# MagController.net
KiCad netlist of a schematic drawn in EAGLE
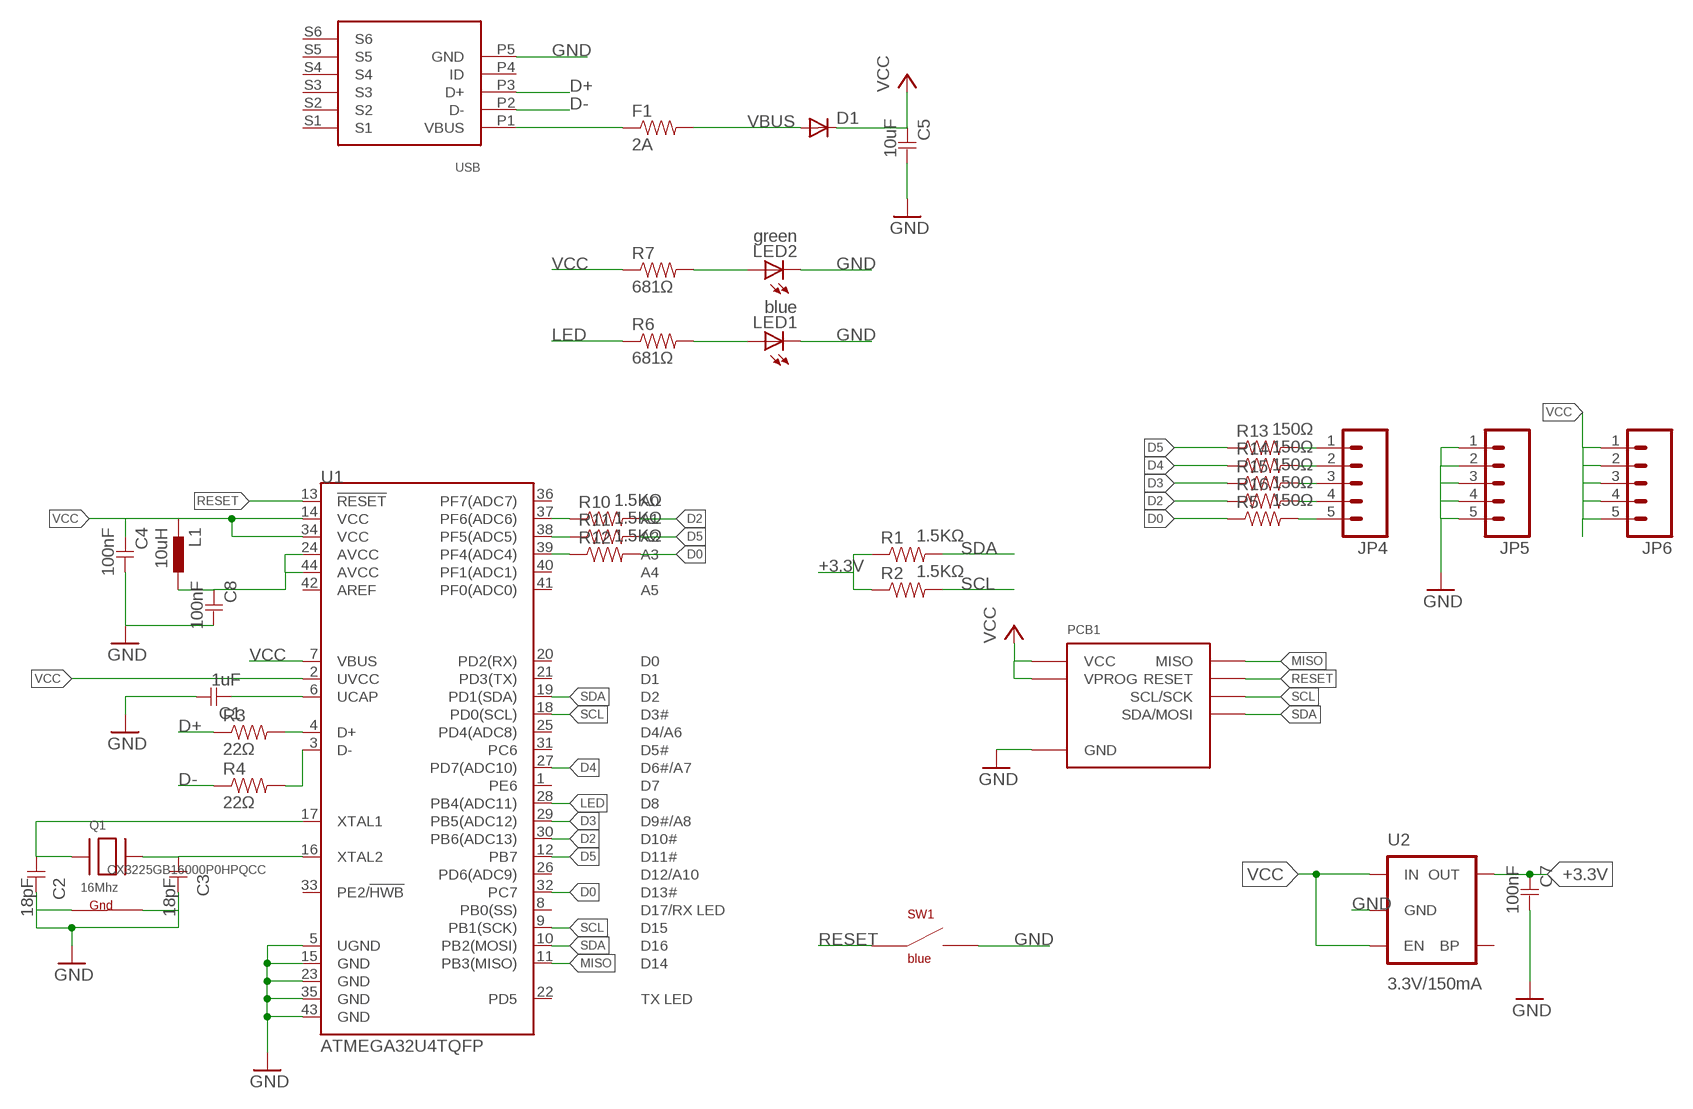
[diagram p0: schematic, sheet 1]

(export (version "E")
  (design (tool "Eeschema 10.0.6"))
  (components
    (comp (ref "C1")
      (value "1uF")
      (footprint "eagle-import:0603")
      (fields (field (name "PARTNUM") "C0603C105K4RACTU"))
      (libsource (lib "eagle-import") (part "CAPACITOR-1UF"))
    )
    (comp (ref "C2")
      (value "18pF")
      (footprint "eagle-import:0603")
      (fields (field (name "PARTNUM") "C0603C180J5GACTU"))
      (libsource (lib "eagle-import") (part "CAPACITOR-18PF"))
    )
    (comp (ref "C3")
      (value "18pF")
      (footprint "eagle-import:0603")
      (fields (field (name "PARTNUM") "C0603C180J5GACTU"))
      (libsource (lib "eagle-import") (part "CAPACITOR-18PF"))
    )
    (comp (ref "C4")
      (value "100nF")
      (footprint "eagle-import:0603")
      (fields (field (name "PARTNUM") "C0603C104K5RACTU"))
      (libsource (lib "eagle-import") (part "CAPACITOR-100NF"))
    )
    (comp (ref "C5")
      (value "10uF")
      (footprint "eagle-import:0603")
      (fields (field (name "PARTNUM") "GRM188R60J106ME47D"))
      (libsource (lib "eagle-import") (part "CAPACITOR-10UF"))
    )
    (comp (ref "C7")
      (value "100nF")
      (footprint "eagle-import:0603")
      (fields (field (name "PARTNUM") "C0603C104K5RACTU"))
      (libsource (lib "eagle-import") (part "CAPACITOR-100NF"))
    )
    (comp (ref "C8")
      (value "100nF")
      (footprint "eagle-import:0603")
      (fields (field (name "PARTNUM") "C0603C104K5RACTU"))
      (libsource (lib "eagle-import") (part "CAPACITOR-100NF"))
    )
    (comp (ref "D1")
      (value "DIODESMA")
      (footprint "eagle-import:SMA-DIODE")
      (fields (field (name "PARTNUM") "SSA33L-E3/61TGICT-ND"))
      (libsource (lib "eagle-import") (part "DIODESMA"))
    )
    (comp (ref "F1")
      (value "2A")
      (footprint "eagle-import:0603")
      (fields (field (name "PARTNUM") "MF-PSMF110X-2"))
      (libsource (lib "eagle-import") (part "RESISTOR-0603"))
    )
    (comp (ref "JP4")
      (value "M05NO_SILK")
      (footprint "eagle-import:1X05_NO_SILK")
      (libsource (lib "eagle-import") (part "M05NO_SILK"))
    )
    (comp (ref "JP5")
      (value "M05NO_SILK")
      (footprint "eagle-import:1X05_NO_SILK")
      (libsource (lib "eagle-import") (part "M05NO_SILK"))
    )
    (comp (ref "JP6")
      (value "M05NO_SILK")
      (footprint "eagle-import:1X05_NO_SILK")
      (libsource (lib "eagle-import") (part "M05NO_SILK"))
    )
    (comp (ref "L1")
      (value "10uH")
      (footprint "eagle-import:0603")
      (fields (field (name "PARTNUM") "LQM18FN100M00"))
      (libsource (lib "eagle-import") (part "INDUCTOR-10UH"))
    )
    (comp (ref "LED1")
      (value "blue")
      (footprint "eagle-import:0805-LED")
      (fields (field (name "PARTNUM") "LTST-C171TBKT"))
      (libsource (lib "eagle-import") (part "LED-0805-BLUE"))
    )
    (comp (ref "LED2")
      (value "green")
      (footprint "eagle-import:0805-LED")
      (fields (field (name "PARTNUM") "LTST-C171GKT"))
      (libsource (lib "eagle-import") (part "LED-0805-GREEN"))
    )
    (comp (ref "PCB1")
      (value "MAGDEVICE")
      (footprint "eagle-import:MAGDEVICE")
      (libsource (lib "eagle-import") (part "MAGDEVICE"))
    )
    (comp (ref "Q1")
      (value "16Mhz")
      (footprint "eagle-import:NX3225")
      (fields (field (name "PARTNUM") "CX3225GB16000P0HPQCC"))
      (libsource (lib "eagle-import") (part "CRYSTAL-NX3225"))
    )
    (comp (ref "R1")
      (value "1.5KΩ")
      (footprint "eagle-import:0603")
      (fields (field (name "PARTNUM") "ERJ-3EKF1501V"))
      (libsource (lib "eagle-import") (part "RESISTOR-1.5KΩ"))
    )
    (comp (ref "R2")
      (value "1.5KΩ")
      (footprint "eagle-import:0603")
      (fields (field (name "PARTNUM") "ERJ-3EKF1501V"))
      (libsource (lib "eagle-import") (part "RESISTOR-1.5KΩ"))
    )
    (comp (ref "R3")
      (value "22Ω")
      (footprint "eagle-import:0603")
      (fields (field (name "PARTNUM") "ERJ-3EKF22R0V"))
      (libsource (lib "eagle-import") (part "RESISTOR-22Ω"))
    )
    (comp (ref "R4")
      (value "22Ω")
      (footprint "eagle-import:0603")
      (fields (field (name "PARTNUM") "ERJ-3EKF22R0V"))
      (libsource (lib "eagle-import") (part "RESISTOR-22Ω"))
    )
    (comp (ref "R5")
      (value "150Ω")
      (footprint "eagle-import:0603")
      (fields (field (name "PARTNUM") "ERJ-3EKF1500V"))
      (libsource (lib "eagle-import") (part "RESISTOR-150Ω"))
    )
    (comp (ref "R6")
      (value "681Ω")
      (footprint "eagle-import:0603")
      (fields (field (name "PARTNUM") "ERJ-3EKF6810V"))
      (libsource (lib "eagle-import") (part "RESISTOR-681Ω"))
    )
    (comp (ref "R7")
      (value "681Ω")
      (footprint "eagle-import:0603")
      (fields (field (name "PARTNUM") "ERJ-3EKF6810V"))
      (libsource (lib "eagle-import") (part "RESISTOR-681Ω"))
    )
    (comp (ref "R10")
      (value "1.5KΩ")
      (footprint "eagle-import:0603")
      (fields (field (name "PARTNUM") "ERJ-3EKF1501V"))
      (libsource (lib "eagle-import") (part "RESISTOR-1.5KΩ"))
    )
    (comp (ref "R11")
      (value "1.5KΩ")
      (footprint "eagle-import:0603")
      (fields (field (name "PARTNUM") "ERJ-3EKF1501V"))
      (libsource (lib "eagle-import") (part "RESISTOR-1.5KΩ"))
    )
    (comp (ref "R12")
      (value "1.5KΩ")
      (footprint "eagle-import:0603")
      (fields (field (name "PARTNUM") "ERJ-3EKF1501V"))
      (libsource (lib "eagle-import") (part "RESISTOR-1.5KΩ"))
    )
    (comp (ref "R13")
      (value "150Ω")
      (footprint "eagle-import:0603")
      (fields (field (name "PARTNUM") "ERJ-3EKF1500V"))
      (libsource (lib "eagle-import") (part "RESISTOR-150Ω"))
    )
    (comp (ref "R14")
      (value "150Ω")
      (footprint "eagle-import:0603")
      (fields (field (name "PARTNUM") "ERJ-3EKF1500V"))
      (libsource (lib "eagle-import") (part "RESISTOR-150Ω"))
    )
    (comp (ref "R15")
      (value "150Ω")
      (footprint "eagle-import:0603")
      (fields (field (name "PARTNUM") "ERJ-3EKF1500V"))
      (libsource (lib "eagle-import") (part "RESISTOR-150Ω"))
    )
    (comp (ref "R16")
      (value "150Ω")
      (footprint "eagle-import:0603")
      (fields (field (name "PARTNUM") "ERJ-3EKF1500V"))
      (libsource (lib "eagle-import") (part "RESISTOR-150Ω"))
    )
    (comp (ref "SW1")
      (value "blue")
      (footprint "eagle-import:BOURNS-7914J")
      (fields (field (name "PARTNUM") "7914J-1-000E"))
      (libsource (lib "eagle-import") (part "SWITCHBOURNS-7914J"))
    )
    (comp (ref "U1")
      (value "ATMEGA32U4TQFP")
      (footprint "eagle-import:SPARKFUN-DIGITALIC_TQFP44")
      (fields (field (name "PARTNUM") "ATMEGA32U4-AU"))
      (libsource (lib "eagle-import") (part "ATMEGA32U4TQFP"))
    )
    (comp (ref "U2")
      (value "3.3V/150mA")
      (footprint "eagle-import:SOT23-5")
      (fields (field (name "PARTNUM") "MIC5205-3.3YM5 TR"))
      (libsource (lib "eagle-import") (part "V_REG_MIC52053.3V"))
    )
    (comp (ref "U3")
      (value "USBFCI-MICROB")
      (footprint "eagle-import:USB-MICROB-FCI")
      (fields (field (name "PARTNUM") "10118194-0001LF"))
      (libsource (lib "eagle-import") (part "USBFCI-MICROB"))
    )
  )
  (nets
    (net (code "1") (name "+3.3V") (class "Default")
      (node (ref "C7") (pin "1") (pinfunction "1_1") (pintype "passive"))
      (node (ref "R1") (pin "1") (pinfunction "1_1") (pintype "passive"))
      (node (ref "R2") (pin "1") (pinfunction "1_1") (pintype "passive"))
      (node (ref "U2") (pin "5") (pinfunction "OUT_5") (pintype "passive"))
    )
    (net (code "2") (name "/D+") (class "Default")
      (node (ref "R3") (pin "1") (pinfunction "1_1") (pintype "passive"))
      (node (ref "U3") (pin "P3") (pinfunction "D+_P3") (pintype "bidirectional"))
    )
    (net (code "3") (name "/D-") (class "Default")
      (node (ref "R4") (pin "1") (pinfunction "1_1") (pintype "passive"))
      (node (ref "U3") (pin "P2") (pinfunction "D-_P2") (pintype "bidirectional"))
    )
    (net (code "4") (name "/VBUS") (class "Default")
      (node (ref "D1") (pin "A") (pinfunction "A_A") (pintype "passive"))
      (node (ref "F1") (pin "2") (pinfunction "2_2") (pintype "passive"))
    )
    (net (code "5") (name "D0") (class "Default")
      (node (ref "R12") (pin "2") (pinfunction "2_2") (pintype "passive"))
      (node (ref "R5") (pin "1") (pinfunction "1_1") (pintype "passive"))
      (node (ref "U1") (pin "32") (pinfunction "PC7_32") (pintype "bidirectional"))
    )
    (net (code "6") (name "D2") (class "Default")
      (node (ref "R10") (pin "2") (pinfunction "2_2") (pintype "passive"))
      (node (ref "R16") (pin "1") (pinfunction "1_1") (pintype "passive"))
      (node (ref "U1") (pin "30") (pinfunction "PB6(ADC13)_30") (pintype "bidirectional"))
    )
    (net (code "7") (name "D3") (class "Default")
      (node (ref "R15") (pin "1") (pinfunction "1_1") (pintype "passive"))
      (node (ref "U1") (pin "29") (pinfunction "PB5(ADC12)_29") (pintype "bidirectional"))
    )
    (net (code "8") (name "D4") (class "Default")
      (node (ref "R14") (pin "1") (pinfunction "1_1") (pintype "passive"))
      (node (ref "U1") (pin "27") (pinfunction "PD7(ADC10)_27") (pintype "bidirectional"))
    )
    (net (code "9") (name "D5") (class "Default")
      (node (ref "R11") (pin "2") (pinfunction "2_2") (pintype "passive"))
      (node (ref "R13") (pin "1") (pinfunction "1_1") (pintype "passive"))
      (node (ref "U1") (pin "12") (pinfunction "PB7_12") (pintype "bidirectional"))
    )
    (net (code "10") (name "GND") (class "Default")
      (node (ref "C1") (pin "2") (pinfunction "2_2") (pintype "passive"))
      (node (ref "C2") (pin "2") (pinfunction "2_2") (pintype "passive"))
      (node (ref "C3") (pin "2") (pinfunction "2_2") (pintype "passive"))
      (node (ref "C4") (pin "2") (pinfunction "2_2") (pintype "passive"))
      (node (ref "C5") (pin "2") (pinfunction "2_2") (pintype "passive"))
      (node (ref "C7") (pin "2") (pinfunction "2_2") (pintype "passive"))
      (node (ref "C8") (pin "2") (pinfunction "2_2") (pintype "passive"))
      (node (ref "JP5") (pin "1") (pinfunction "1_1") (pintype "passive"))
      (node (ref "JP5") (pin "2") (pinfunction "2_2") (pintype "passive"))
      (node (ref "JP5") (pin "3") (pinfunction "3_3") (pintype "passive"))
      (node (ref "JP5") (pin "4") (pinfunction "4_4") (pintype "passive"))
      (node (ref "JP5") (pin "5") (pinfunction "5_5") (pintype "passive"))
      (node (ref "LED1") (pin "C") (pinfunction "C_C") (pintype "passive"))
      (node (ref "LED2") (pin "C") (pinfunction "C_C") (pintype "passive"))
      (node (ref "PCB1") (pin "GNDA") (pinfunction "GND_GNDA") (pintype "bidirectional"))
      (node (ref "PCB1") (pin "GNDB") (pinfunction "GND_GNDB") (pintype "bidirectional"))
      (node (ref "Q1") (pin "2") (pinfunction "G1_2") (pintype "power_in"))
      (node (ref "Q1") (pin "4") (pinfunction "G2_4") (pintype "power_in"))
      (node (ref "SW1") (pin "NEG$1") (pinfunction "NEG1_NEG$1") (pintype "bidirectional"))
      (node (ref "SW1") (pin "NEG$2") (pinfunction "NEG1_NEG$2") (pintype "bidirectional"))
      (node (ref "U1") (pin "15") (pinfunction "GND_15") (pintype "bidirectional"))
      (node (ref "U1") (pin "23") (pinfunction "GND_23") (pintype "bidirectional"))
      (node (ref "U1") (pin "35") (pinfunction "GND_35") (pintype "bidirectional"))
      (node (ref "U1") (pin "43") (pinfunction "GND_43") (pintype "bidirectional"))
      (node (ref "U1") (pin "5") (pinfunction "UGND_5") (pintype "bidirectional"))
      (node (ref "U2") (pin "2") (pinfunction "GND_2") (pintype "input"))
      (node (ref "U3") (pin "P5") (pinfunction "GND_P5") (pintype "bidirectional"))
    )
    (net (code "11") (name "LED") (class "Default")
      (node (ref "R6") (pin "1") (pinfunction "1_1") (pintype "passive"))
      (node (ref "U1") (pin "28") (pinfunction "PB4(ADC11)_28") (pintype "bidirectional"))
    )
    (net (code "12") (name "MISO") (class "Default")
      (node (ref "PCB1") (pin "MISO") (pinfunction "MISO_MISO") (pintype "bidirectional"))
      (node (ref "U1") (pin "11") (pinfunction "PB3(MISO)_11") (pintype "bidirectional"))
    )
    (net (code "13") (name "Net-(C8-Pad1)") (class "Default")
      (node (ref "C8") (pin "1") (pinfunction "1_1") (pintype "passive"))
      (node (ref "L1") (pin "2") (pinfunction "2_2") (pintype "passive"))
      (node (ref "U1") (pin "24") (pinfunction "AVCC_24") (pintype "bidirectional"))
      (node (ref "U1") (pin "44") (pinfunction "AVCC_44") (pintype "bidirectional"))
    )
    (net (code "14") (name "Net-(JP4-Pad1)") (class "Default")
      (node (ref "JP4") (pin "1") (pinfunction "1_1") (pintype "passive"))
      (node (ref "R13") (pin "2") (pinfunction "2_2") (pintype "passive"))
    )
    (net (code "15") (name "Net-(JP4-Pad2)") (class "Default")
      (node (ref "JP4") (pin "2") (pinfunction "2_2") (pintype "passive"))
      (node (ref "R14") (pin "2") (pinfunction "2_2") (pintype "passive"))
    )
    (net (code "16") (name "Net-(JP4-Pad3)") (class "Default")
      (node (ref "JP4") (pin "3") (pinfunction "3_3") (pintype "passive"))
      (node (ref "R15") (pin "2") (pinfunction "2_2") (pintype "passive"))
    )
    (net (code "17") (name "Net-(JP4-Pad4)") (class "Default")
      (node (ref "JP4") (pin "4") (pinfunction "4_4") (pintype "passive"))
      (node (ref "R16") (pin "2") (pinfunction "2_2") (pintype "passive"))
    )
    (net (code "18") (name "Net-(JP4-Pad5)") (class "Default")
      (node (ref "JP4") (pin "5") (pinfunction "5_5") (pintype "passive"))
      (node (ref "R5") (pin "2") (pinfunction "2_2") (pintype "passive"))
    )
    (net (code "19") (name "Net-(LED1-PadA)") (class "Default")
      (node (ref "LED1") (pin "A") (pinfunction "A_A") (pintype "passive"))
      (node (ref "R6") (pin "2") (pinfunction "2_2") (pintype "passive"))
    )
    (net (code "20") (name "Net-(LED2-PadA)") (class "Default")
      (node (ref "LED2") (pin "A") (pinfunction "A_A") (pintype "passive"))
      (node (ref "R7") (pin "2") (pinfunction "2_2") (pintype "passive"))
    )
    (net (code "21") (name "Net-(Q1-X1)") (class "Default")
      (node (ref "C2") (pin "1") (pinfunction "1_1") (pintype "passive"))
      (node (ref "Q1") (pin "1") (pinfunction "X1_1") (pintype "bidirectional"))
      (node (ref "U1") (pin "17") (pinfunction "XTAL1_17") (pintype "bidirectional"))
    )
    (net (code "22") (name "Net-(Q1-X2)") (class "Default")
      (node (ref "C3") (pin "1") (pinfunction "1_1") (pintype "passive"))
      (node (ref "Q1") (pin "3") (pinfunction "X2_3") (pintype "bidirectional"))
      (node (ref "U1") (pin "16") (pinfunction "XTAL2_16") (pintype "bidirectional"))
    )
    (net (code "23") (name "Net-(U1-D+)") (class "Default")
      (node (ref "R3") (pin "2") (pinfunction "2_2") (pintype "passive"))
      (node (ref "U1") (pin "4") (pinfunction "D+_4") (pintype "bidirectional"))
    )
    (net (code "24") (name "Net-(U1-D-)") (class "Default")
      (node (ref "R4") (pin "2") (pinfunction "2_2") (pintype "passive"))
      (node (ref "U1") (pin "3") (pinfunction "D-_3") (pintype "bidirectional"))
    )
    (net (code "25") (name "Net-(U1-PF4(ADC4))") (class "Default")
      (node (ref "R12") (pin "1") (pinfunction "1_1") (pintype "passive"))
      (node (ref "U1") (pin "39") (pinfunction "PF4(ADC4)_39") (pintype "bidirectional"))
    )
    (net (code "26") (name "Net-(U1-PF5(ADC5))") (class "Default")
      (node (ref "R11") (pin "1") (pinfunction "1_1") (pintype "passive"))
      (node (ref "U1") (pin "38") (pinfunction "PF5(ADC5)_38") (pintype "bidirectional"))
    )
    (net (code "27") (name "Net-(U1-PF6(ADC6))") (class "Default")
      (node (ref "R10") (pin "1") (pinfunction "1_1") (pintype "passive"))
      (node (ref "U1") (pin "37") (pinfunction "PF6(ADC6)_37") (pintype "bidirectional"))
    )
    (net (code "28") (name "Net-(U1-UCAP)") (class "Default")
      (node (ref "C1") (pin "1") (pinfunction "1_1") (pintype "passive"))
      (node (ref "U1") (pin "6") (pinfunction "UCAP_6") (pintype "bidirectional"))
    )
    (net (code "29") (name "Net-(U3-VBUS)") (class "Default")
      (node (ref "F1") (pin "1") (pinfunction "1_1") (pintype "passive"))
      (node (ref "U3") (pin "P1") (pinfunction "VBUS_P1") (pintype "bidirectional"))
    )
    (net (code "30") (name "RESET") (class "Default")
      (node (ref "PCB1") (pin "RESET") (pinfunction "RESET_RESET") (pintype "bidirectional"))
      (node (ref "SW1") (pin "POS$1") (pinfunction "POS1_POS$1") (pintype "bidirectional"))
      (node (ref "SW1") (pin "POS$2") (pinfunction "POS1_POS$2") (pintype "bidirectional"))
      (node (ref "U1") (pin "13") (pinfunction "~{RESET}_13") (pintype "bidirectional"))
    )
    (net (code "31") (name "SCL") (class "Default")
      (node (ref "PCB1") (pin "SCLA") (pinfunction "SCL/SCK_SCLA") (pintype "bidirectional"))
      (node (ref "PCB1") (pin "SCLB") (pinfunction "SCL/SCK_SCLB") (pintype "bidirectional"))
      (node (ref "R2") (pin "2") (pinfunction "2_2") (pintype "passive"))
      (node (ref "U1") (pin "18") (pinfunction "PD0(SCL)_18") (pintype "bidirectional"))
      (node (ref "U1") (pin "9") (pinfunction "PB1(SCK)_9") (pintype "bidirectional"))
    )
    (net (code "32") (name "SDA") (class "Default")
      (node (ref "PCB1") (pin "SDAA") (pinfunction "SDA/MOSI_SDAA") (pintype "bidirectional"))
      (node (ref "PCB1") (pin "SDAB") (pinfunction "SDA/MOSI_SDAB") (pintype "bidirectional"))
      (node (ref "R1") (pin "2") (pinfunction "2_2") (pintype "passive"))
      (node (ref "U1") (pin "10") (pinfunction "PB2(MOSI)_10") (pintype "bidirectional"))
      (node (ref "U1") (pin "19") (pinfunction "PD1(SDA)_19") (pintype "bidirectional"))
    )
    (net (code "33") (name "VCC") (class "Default")
      (node (ref "C4") (pin "1") (pinfunction "1_1") (pintype "passive"))
      (node (ref "C5") (pin "1") (pinfunction "1_1") (pintype "passive"))
      (node (ref "D1") (pin "C") (pinfunction "C_C") (pintype "passive"))
      (node (ref "JP6") (pin "1") (pinfunction "1_1") (pintype "passive"))
      (node (ref "JP6") (pin "2") (pinfunction "2_2") (pintype "passive"))
      (node (ref "JP6") (pin "3") (pinfunction "3_3") (pintype "passive"))
      (node (ref "JP6") (pin "4") (pinfunction "4_4") (pintype "passive"))
      (node (ref "JP6") (pin "5") (pinfunction "5_5") (pintype "passive"))
      (node (ref "L1") (pin "1") (pinfunction "1_1") (pintype "passive"))
      (node (ref "PCB1") (pin "VCCA") (pinfunction "VCC_VCCA") (pintype "bidirectional"))
      (node (ref "PCB1") (pin "VCCB") (pinfunction "VCC_VCCB") (pintype "bidirectional"))
      (node (ref "PCB1") (pin "VPROG") (pinfunction "VPROG_VPROG") (pintype "bidirectional"))
      (node (ref "R7") (pin "1") (pinfunction "1_1") (pintype "passive"))
      (node (ref "U1") (pin "14") (pinfunction "VCC_14") (pintype "bidirectional"))
      (node (ref "U1") (pin "2") (pinfunction "UVCC_2") (pintype "bidirectional"))
      (node (ref "U1") (pin "34") (pinfunction "VCC_34") (pintype "bidirectional"))
      (node (ref "U1") (pin "7") (pinfunction "VBUS_7") (pintype "bidirectional"))
      (node (ref "U2") (pin "1") (pinfunction "IN_1") (pintype "input"))
      (node (ref "U2") (pin "3") (pinfunction "EN_3") (pintype "input"))
    )
    (net (code "34") (name "unconnected-(U1-AREF-Pad42)") (class "Default")
      (node (ref "U1") (pin "42") (pinfunction "AREF_42") (pintype "bidirectional"))
    )
    (net (code "35") (name "unconnected-(U1-PB0(SS)-Pad8)") (class "Default")
      (node (ref "U1") (pin "8") (pinfunction "PB0(SS)_8") (pintype "bidirectional"))
    )
    (net (code "36") (name "unconnected-(U1-PC6-Pad31)") (class "Default")
      (node (ref "U1") (pin "31") (pinfunction "PC6_31") (pintype "bidirectional"))
    )
    (net (code "37") (name "unconnected-(U1-PD2(RX)-Pad20)") (class "Default")
      (node (ref "U1") (pin "20") (pinfunction "PD2(RX)_20") (pintype "bidirectional"))
    )
    (net (code "38") (name "unconnected-(U1-PD3(TX)-Pad21)") (class "Default")
      (node (ref "U1") (pin "21") (pinfunction "PD3(TX)_21") (pintype "bidirectional"))
    )
    (net (code "39") (name "unconnected-(U1-PD4(ADC8)-Pad25)") (class "Default")
      (node (ref "U1") (pin "25") (pinfunction "PD4(ADC8)_25") (pintype "bidirectional"))
    )
    (net (code "40") (name "unconnected-(U1-PD5-Pad22)") (class "Default")
      (node (ref "U1") (pin "22") (pinfunction "PD5_22") (pintype "bidirectional"))
    )
    (net (code "41") (name "unconnected-(U1-PD6(ADC9)-Pad26)") (class "Default")
      (node (ref "U1") (pin "26") (pinfunction "PD6(ADC9)_26") (pintype "bidirectional"))
    )
    (net (code "42") (name "unconnected-(U1-PE2{slash}~{HWB}-Pad33)") (class "Default")
      (node (ref "U1") (pin "33") (pinfunction "PE2/~{HWB}_33") (pintype "bidirectional"))
    )
    (net (code "43") (name "unconnected-(U1-PE6-Pad1)") (class "Default")
      (node (ref "U1") (pin "1") (pinfunction "PE6_1") (pintype "bidirectional"))
    )
    (net (code "44") (name "unconnected-(U1-PF0(ADC0)-Pad41)") (class "Default")
      (node (ref "U1") (pin "41") (pinfunction "PF0(ADC0)_41") (pintype "bidirectional"))
    )
    (net (code "45") (name "unconnected-(U1-PF1(ADC1)-Pad40)") (class "Default")
      (node (ref "U1") (pin "40") (pinfunction "PF1(ADC1)_40") (pintype "bidirectional"))
    )
    (net (code "46") (name "unconnected-(U1-PF7(ADC7)-Pad36)") (class "Default")
      (node (ref "U1") (pin "36") (pinfunction "PF7(ADC7)_36") (pintype "bidirectional"))
    )
    (net (code "47") (name "unconnected-(U2-BP-Pad4)") (class "Default")
      (node (ref "U2") (pin "4") (pinfunction "BP_4") (pintype "input"))
    )
    (net (code "48") (name "unconnected-(U3-ID-PadP4)") (class "Default")
      (node (ref "U3") (pin "P4") (pinfunction "ID_P4") (pintype "bidirectional"))
    )
    (net (code "49") (name "unconnected-(U3-PadS1)") (class "Default")
      (node (ref "U3") (pin "S1") (pinfunction "S1_S1") (pintype "bidirectional"))
    )
    (net (code "50") (name "unconnected-(U3-PadS2)") (class "Default")
      (node (ref "U3") (pin "S2") (pinfunction "S2_S2") (pintype "bidirectional"))
    )
    (net (code "51") (name "unconnected-(U3-PadS3)") (class "Default")
      (node (ref "U3") (pin "S3") (pinfunction "S3_S3") (pintype "bidirectional"))
    )
    (net (code "52") (name "unconnected-(U3-PadS4)") (class "Default")
      (node (ref "U3") (pin "S4") (pinfunction "S4_S4") (pintype "bidirectional"))
    )
    (net (code "53") (name "unconnected-(U3-PadS5)") (class "Default")
      (node (ref "U3") (pin "S5") (pinfunction "S5_S5") (pintype "bidirectional"))
    )
    (net (code "54") (name "unconnected-(U3-PadS6)") (class "Default")
      (node (ref "U3") (pin "S6") (pinfunction "S6_S6") (pintype "bidirectional"))
    )
  )
)
